# EMI_FILTER.net
KiCad netlist of a schematic drawn in Altium Designer
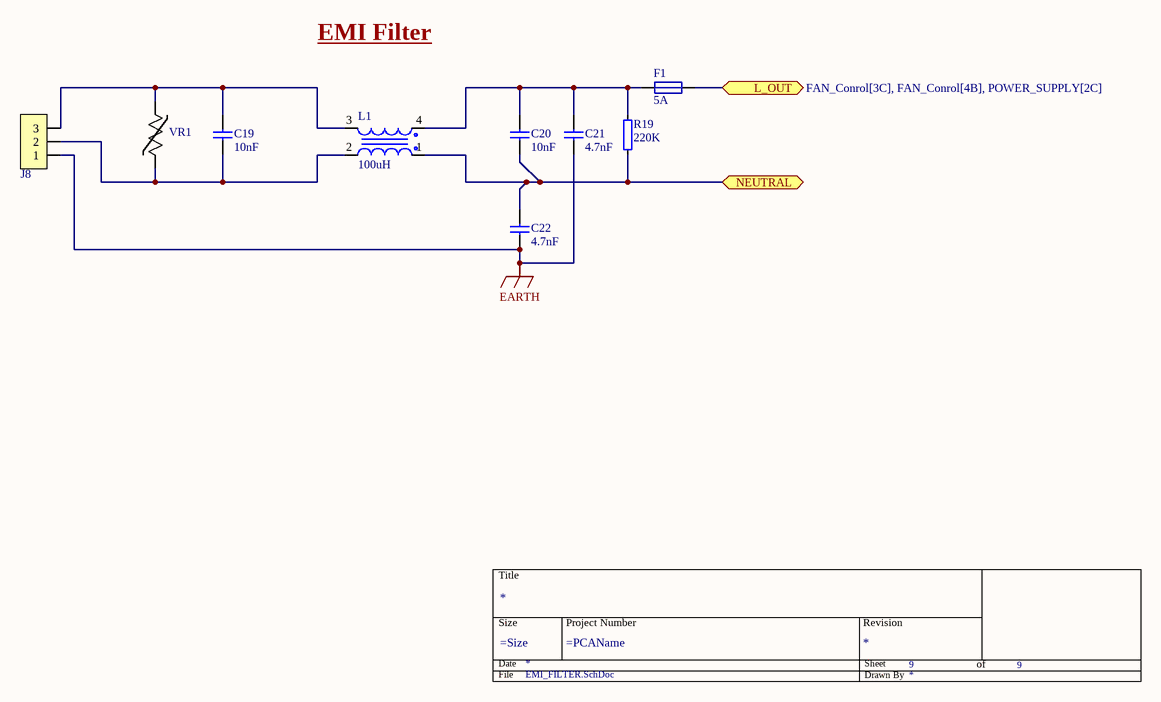
[diagram p0: EMI_FILTER.SchDoc]

(export (version "E")
  (design (tool "Eeschema 10.0.6"))
  (components
    (comp (ref "*") (value "Title Block") (libsource (lib "HEPA_LIB") (part "Title Block")))
    (comp (ref "C19")
      (value "10nF")
      (footprint "CAPRR1500W60L1850T800H1650")
      (description "Capacitor, Metalized Polypropylene Film,300VAC, 10nF, +-10%")
      (fields (field (name "PART NUMBER") "10nF 300V") (field (name "PUBLISHER") "Metal Circuits"))
      (libsource (lib "HEPA_LIB") (part "0.1uF 300V"))
    )
    (comp (ref "C20")
      (value "10nF")
      (footprint "CAPRR1500W60L1850T800H1650")
      (description "Capacitor, Metalized Polypropylene Film,300VAC, 10nF, +-10%")
      (fields (field (name "PART NUMBER") "10nF 300V") (field (name "PUBLISHER") "Metal Circuits"))
      (libsource (lib "HEPA_LIB") (part "0.1uF 300V"))
    )
    (comp (ref "C21")
      (value "4.7nF")
      (footprint "CAPRR1500W60L1850T800H1650")
      (description "Capacitor, Metalized Polypropylene Film,300VAC, 4.7nF, +-10%")
      (fields (field (name "PART NUMBER") "4.7nF 300V") (field (name "PUBLISHER") "Metal Circuits"))
      (libsource (lib "HEPA_LIB") (part "0.1uF 300V"))
    )
    (comp (ref "C22")
      (value "4.7nF")
      (footprint "CAPRR1500W60L1850T800H1650")
      (description "Capacitor, Metalized Polypropylene Film,300VAC, 4.7nF, +-10%")
      (fields (field (name "PART NUMBER") "4.7nF 300V") (field (name "PUBLISHER") "Metal Circuits"))
      (libsource (lib "HEPA_LIB") (part "0.1uF 300V"))
    )
    (comp (ref "F1")
      (value "5A")
      (footprint "Fuse 5X20mm")
      (description "5x20 Fuse Holders ROHS")
      (fields (field (name "PART NUMBER") "Fuse Holder") (field (name "PUBLISHER") "Metal Circuits"))
      (libsource (lib "HEPA_LIB") (part "Fuse"))
    )
    (comp (ref "J8")
      (value "1935174")
      (footprint "PHOENIX_1935174")
      (description "3 Position Wire to Board Terminal Block Horizontal with Board 0.197\" (5.00mm) Through Hole")
      (fields (field (name "MANUFACTURER") "Phoenix Contact") (field (name "PUBLISHER") "Metal Circuits"))
      (libsource (lib "HEPA_LIB") (part "1935174"))
    )
    (comp (ref "L1")
      (value "100uH")
      (footprint "UU10.5-10mH")
      (description "100uH@1kHz 1.5Ω 2 Plugin Common Mode Filters ROHS")
      (fields
        (field (name "PART NUMBER") "UU10.5-100uH")
        (field (name "MANUFACTURER") "FH (Guangdong Fenghua Advanced Tech)")
        (field (name "PUBLISHER") "Metal Circuits")
      )
      (libsource (lib "Integrated_Library_Altium") (part "UU10.5-10mH"))
    )
    (comp (ref "R19")
      (value "220K")
      (footprint "RES_ROX2S_TYCO_TYC")
      (description "Carbon Film Through Hole Resistor 1Watt 1%")
      (fields (field (name "PART NUMBER") "RES 1 Watt") (field (name "PUBLISHER") "Metal Circuits"))
      (libsource (lib "HEPA_LIB") (part "RES 1Watt"))
    )
    (comp (ref "VR1")
      (value "S14K561")
      (footprint "VRES_B72214_2301_EPC")
      (description "Tv - Varistors, Mov Circuit Protection 4.5kA 470V")
      (fields (field (name "PUBLISHER") "Metal Circuits"))
      (libsource (lib "HEPA_LIB") (part "S14K230"))
    )
  )
  (nets
    (net (code "1") (name "/L_OUT") (class "Default")
      (node (ref "F1") (pin "2") (pinfunction "2_2") (pintype "passive"))
    )
    (net (code "2") (name "/NEUTRAL") (class "Default")
      (node (ref "C20") (pin "1") (pinfunction "1_1") (pintype "passive"))
      (node (ref "C22") (pin "2") (pinfunction "2_2") (pintype "passive"))
      (node (ref "L1") (pin "1") (pinfunction "1_1") (pintype "passive"))
      (node (ref "R19") (pin "1") (pinfunction "1_1") (pintype "passive"))
    )
    (net (code "3") (name "EARTH") (class "Default")
      (node (ref "C21") (pin "1") (pinfunction "1_1") (pintype "passive"))
      (node (ref "C22") (pin "1") (pinfunction "1_1") (pintype "passive"))
      (node (ref "J8") (pin "1") (pinfunction "1_1") (pintype "passive"))
    )
    (net (code "4") (name "Net-(C20-Pad2)") (class "Default")
      (node (ref "C20") (pin "2") (pinfunction "2_2") (pintype "passive"))
      (node (ref "C21") (pin "2") (pinfunction "2_2") (pintype "passive"))
      (node (ref "F1") (pin "1") (pinfunction "1_1") (pintype "passive"))
      (node (ref "L1") (pin "4") (pinfunction "4_4") (pintype "passive"))
      (node (ref "R19") (pin "2") (pinfunction "2_2") (pintype "passive"))
    )
    (net (code "5") (name "Net-(VR1-11)") (class "Default")
      (node (ref "C19") (pin "2") (pinfunction "2_2") (pintype "passive"))
      (node (ref "J8") (pin "3") (pinfunction "3_3") (pintype "passive"))
      (node (ref "L1") (pin "3") (pinfunction "3_3") (pintype "passive"))
      (node (ref "VR1") (pin "1") (pinfunction "11_1") (pintype "passive"))
    )
    (net (code "6") (name "Net-(VR1-12)") (class "Default")
      (node (ref "C19") (pin "1") (pinfunction "1_1") (pintype "passive"))
      (node (ref "J8") (pin "2") (pinfunction "2_2") (pintype "passive"))
      (node (ref "L1") (pin "2") (pinfunction "2_2") (pintype "passive"))
      (node (ref "VR1") (pin "2") (pinfunction "12_2") (pintype "passive"))
    )
  )
)
